# MCU.net
KiCad netlist of a schematic drawn in Altium Designer
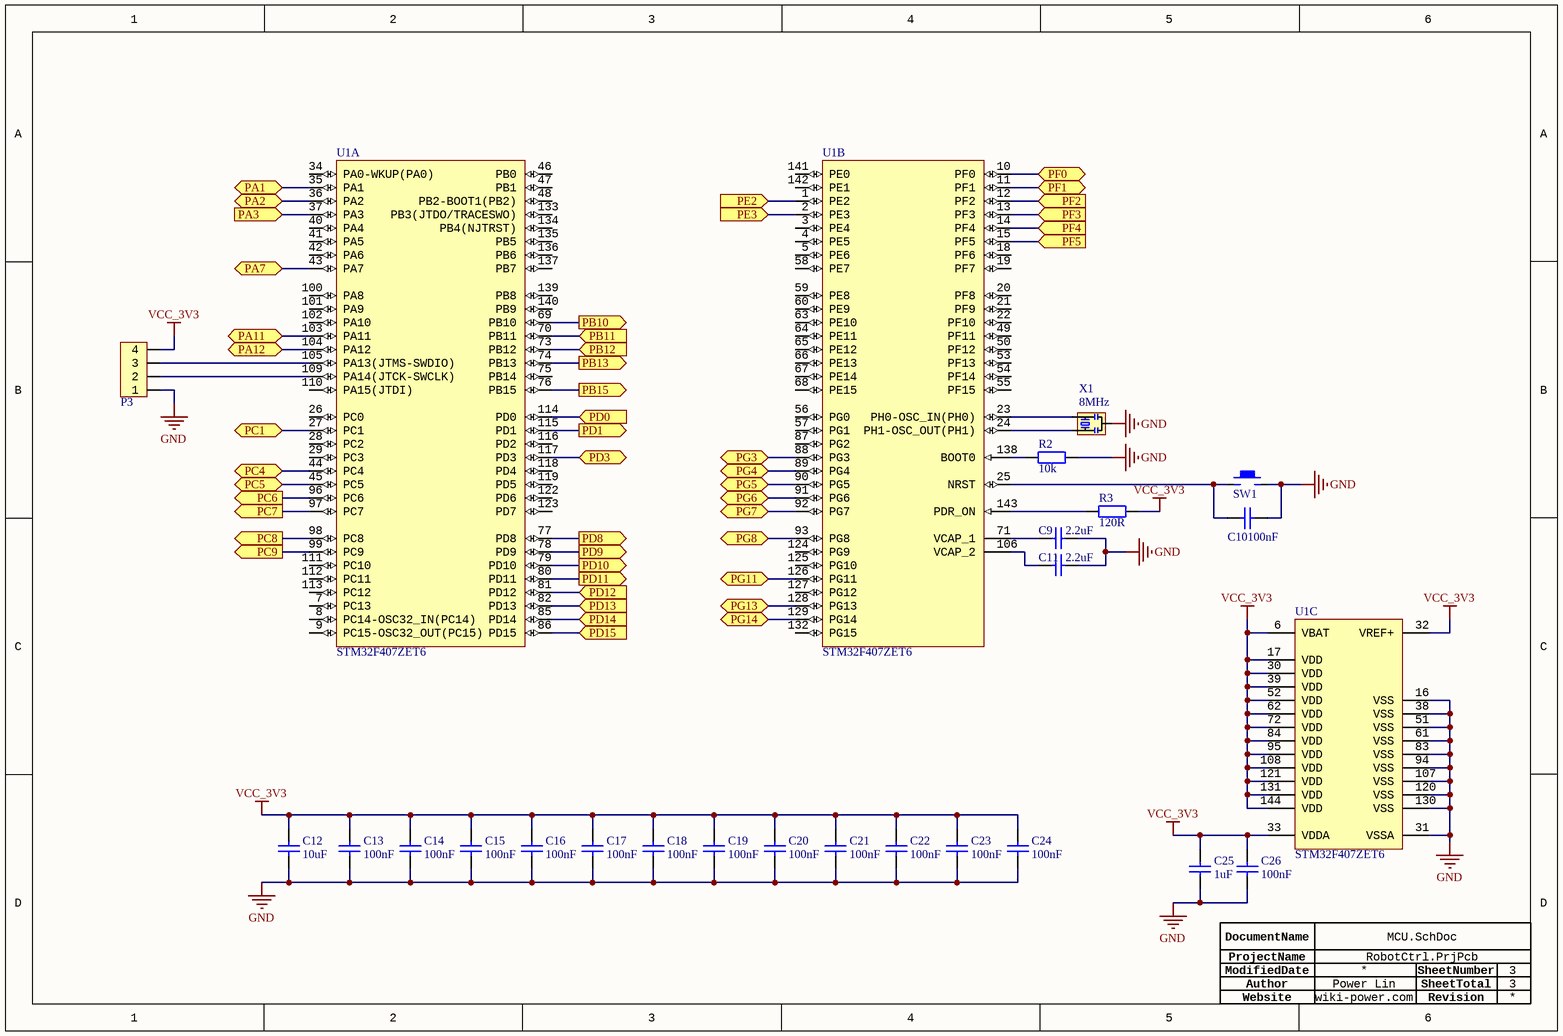
[diagram p0: MCU.SchDoc]

(export (version "E")
  (design (tool "Eeschema 10.0.6"))
  (components
    (comp (ref "C9")
      (value "2.2uF")
      (footprint "CAP-0603")
      (description "贴片电容")
      (libsource (lib "Power_Lib_Altium") (part "CAP"))
    )
    (comp (ref "C10")
      (value "100nF")
      (footprint "CAP-0603")
      (description "贴片电容")
      (libsource (lib "Power_Lib_Altium") (part "CAP"))
    )
    (comp (ref "C11")
      (value "2.2uF")
      (footprint "CAP-0603")
      (description "贴片电容")
      (libsource (lib "Power_Lib_Altium") (part "CAP"))
    )
    (comp (ref "C12")
      (value "10uF")
      (footprint "CAP-0603")
      (description "贴片电容")
      (libsource (lib "Power_Lib_Altium") (part "CAP"))
    )
    (comp (ref "C13")
      (value "100nF")
      (footprint "CAP-0603")
      (description "贴片电容")
      (libsource (lib "Power_Lib_Altium") (part "CAP"))
    )
    (comp (ref "C14")
      (value "100nF")
      (footprint "CAP-0603")
      (description "贴片电容")
      (libsource (lib "Power_Lib_Altium") (part "CAP"))
    )
    (comp (ref "C15")
      (value "100nF")
      (footprint "CAP-0603")
      (description "贴片电容")
      (libsource (lib "Power_Lib_Altium") (part "CAP"))
    )
    (comp (ref "C16")
      (value "100nF")
      (footprint "CAP-0603")
      (description "贴片电容")
      (libsource (lib "Power_Lib_Altium") (part "CAP"))
    )
    (comp (ref "C17")
      (value "100nF")
      (footprint "CAP-0603")
      (description "贴片电容")
      (libsource (lib "Power_Lib_Altium") (part "CAP"))
    )
    (comp (ref "C18")
      (value "100nF")
      (footprint "CAP-0603")
      (description "贴片电容")
      (libsource (lib "Power_Lib_Altium") (part "CAP"))
    )
    (comp (ref "C19")
      (value "100nF")
      (footprint "CAP-0603")
      (description "贴片电容")
      (libsource (lib "Power_Lib_Altium") (part "CAP"))
    )
    (comp (ref "C20")
      (value "100nF")
      (footprint "CAP-0603")
      (description "贴片电容")
      (libsource (lib "Power_Lib_Altium") (part "CAP"))
    )
    (comp (ref "C21")
      (value "100nF")
      (footprint "CAP-0603")
      (description "贴片电容")
      (libsource (lib "Power_Lib_Altium") (part "CAP"))
    )
    (comp (ref "C22")
      (value "100nF")
      (footprint "CAP-0603")
      (description "贴片电容")
      (libsource (lib "Power_Lib_Altium") (part "CAP"))
    )
    (comp (ref "C23")
      (value "100nF")
      (footprint "CAP-0603")
      (description "贴片电容")
      (libsource (lib "Power_Lib_Altium") (part "CAP"))
    )
    (comp (ref "C24")
      (value "100nF")
      (footprint "CAP-0603")
      (description "贴片电容")
      (libsource (lib "Power_Lib_Altium") (part "CAP"))
    )
    (comp (ref "C25")
      (value "1uF")
      (footprint "CAP-0603")
      (description "贴片电容")
      (libsource (lib "Power_Lib_Altium") (part "CAP"))
    )
    (comp (ref "C26")
      (value "100nF")
      (footprint "CAP-0603")
      (description "贴片电容")
      (libsource (lib "Power_Lib_Altium") (part "CAP"))
    )
    (comp (ref "P3")
      (value "HDR1x4_2.54")
      (footprint "HDR1x4_2.54_180")
      (description "Header")
      (libsource (lib "Power_Lib_Altium") (part "HDR1x4_2.54"))
    )
    (comp (ref "R2")
      (value "10k")
      (footprint "R-0603")
      (description "贴片电阻")
      (libsource (lib "Power_Lib_Altium") (part "RES"))
    )
    (comp (ref "R3")
      (value "120R")
      (footprint "R-0603")
      (description "贴片电阻")
      (libsource (lib "Power_Lib_Altium") (part "RES"))
    )
    (comp (ref "SW1")
      (value "KEY")
      (footprint "KEY-4P-4.2*3.4*2.5")
      (description "按键开关")
      (libsource (lib "Power_Lib_Altium") (part "KEY"))
    )
    (comp (ref "U1")
      (value "STM32F407ZET6")
      (footprint "STM-LQFP144_N")
      (fields (field (name "MANUFACTURER") "STMicroelectronics"))
      (libsource (lib "STMicroelectronics STM32 F4") (part "STM32F407ZET6"))
    )
    (comp (ref "X1")
      (value "8MHz")
      (footprint "SMD3213-3P")
      (description "CSTCE8M00G15C99-R0")
      (libsource (lib "Power_Lib_Altium") (part "XTAL"))
    )
  )
  (nets
    (net (code "1") (name "/PA1") (class "Default")
      (node (ref "U1") (pin "35") (pinfunction "PA1_35") (pintype "bidirectional"))
    )
    (net (code "2") (name "/PA2") (class "Default")
      (node (ref "U1") (pin "36") (pinfunction "PA2_36") (pintype "bidirectional"))
    )
    (net (code "3") (name "/PA3") (class "Default")
      (node (ref "U1") (pin "37") (pinfunction "PA3_37") (pintype "bidirectional"))
    )
    (net (code "4") (name "/PA7") (class "Default")
      (node (ref "U1") (pin "43") (pinfunction "PA7_43") (pintype "bidirectional"))
    )
    (net (code "5") (name "/PA11") (class "Default")
      (node (ref "U1") (pin "103") (pinfunction "PA11_103") (pintype "bidirectional"))
    )
    (net (code "6") (name "/PA12") (class "Default")
      (node (ref "U1") (pin "104") (pinfunction "PA12_104") (pintype "bidirectional"))
    )
    (net (code "7") (name "/PB10") (class "Default")
      (node (ref "U1") (pin "69") (pinfunction "PB10_69") (pintype "bidirectional"))
    )
    (net (code "8") (name "/PB11") (class "Default")
      (node (ref "U1") (pin "70") (pinfunction "PB11_70") (pintype "bidirectional"))
    )
    (net (code "9") (name "/PB12") (class "Default")
      (node (ref "U1") (pin "73") (pinfunction "PB12_73") (pintype "bidirectional"))
    )
    (net (code "10") (name "/PB13") (class "Default")
      (node (ref "U1") (pin "74") (pinfunction "PB13_74") (pintype "bidirectional"))
    )
    (net (code "11") (name "/PB15") (class "Default")
      (node (ref "U1") (pin "76") (pinfunction "PB15_76") (pintype "bidirectional"))
    )
    (net (code "12") (name "/PC1") (class "Default")
      (node (ref "U1") (pin "27") (pinfunction "PC1_27") (pintype "bidirectional"))
    )
    (net (code "13") (name "/PC4") (class "Default")
      (node (ref "U1") (pin "44") (pinfunction "PC4_44") (pintype "bidirectional"))
    )
    (net (code "14") (name "/PC5") (class "Default")
      (node (ref "U1") (pin "45") (pinfunction "PC5_45") (pintype "bidirectional"))
    )
    (net (code "15") (name "/PC6") (class "Default")
      (node (ref "U1") (pin "96") (pinfunction "PC6_96") (pintype "bidirectional"))
    )
    (net (code "16") (name "/PC7") (class "Default")
      (node (ref "U1") (pin "97") (pinfunction "PC7_97") (pintype "bidirectional"))
    )
    (net (code "17") (name "/PC8") (class "Default")
      (node (ref "U1") (pin "98") (pinfunction "PC8_98") (pintype "bidirectional"))
    )
    (net (code "18") (name "/PC9") (class "Default")
      (node (ref "U1") (pin "99") (pinfunction "PC9_99") (pintype "bidirectional"))
    )
    (net (code "19") (name "/PD0") (class "Default")
      (node (ref "U1") (pin "114") (pinfunction "PD0_114") (pintype "bidirectional"))
    )
    (net (code "20") (name "/PD1") (class "Default")
      (node (ref "U1") (pin "115") (pinfunction "PD1_115") (pintype "bidirectional"))
    )
    (net (code "21") (name "/PD3") (class "Default")
      (node (ref "U1") (pin "117") (pinfunction "PD3_117") (pintype "bidirectional"))
    )
    (net (code "22") (name "/PD8") (class "Default")
      (node (ref "U1") (pin "77") (pinfunction "PD8_77") (pintype "bidirectional"))
    )
    (net (code "23") (name "/PD9") (class "Default")
      (node (ref "U1") (pin "78") (pinfunction "PD9_78") (pintype "bidirectional"))
    )
    (net (code "24") (name "/PD10") (class "Default")
      (node (ref "U1") (pin "79") (pinfunction "PD10_79") (pintype "bidirectional"))
    )
    (net (code "25") (name "/PD11") (class "Default")
      (node (ref "U1") (pin "80") (pinfunction "PD11_80") (pintype "bidirectional"))
    )
    (net (code "26") (name "/PD12") (class "Default")
      (node (ref "U1") (pin "81") (pinfunction "PD12_81") (pintype "bidirectional"))
    )
    (net (code "27") (name "/PD13") (class "Default")
      (node (ref "U1") (pin "82") (pinfunction "PD13_82") (pintype "bidirectional"))
    )
    (net (code "28") (name "/PD14") (class "Default")
      (node (ref "U1") (pin "85") (pinfunction "PD14_85") (pintype "bidirectional"))
    )
    (net (code "29") (name "/PD15") (class "Default")
      (node (ref "U1") (pin "86") (pinfunction "PD15_86") (pintype "bidirectional"))
    )
    (net (code "30") (name "/PE2") (class "Default")
      (node (ref "U1") (pin "1") (pinfunction "PE2_1") (pintype "bidirectional"))
    )
    (net (code "31") (name "/PE3") (class "Default")
      (node (ref "U1") (pin "2") (pinfunction "PE3_2") (pintype "bidirectional"))
    )
    (net (code "32") (name "/PF0") (class "Default")
      (node (ref "U1") (pin "10") (pinfunction "PF0_10") (pintype "bidirectional"))
    )
    (net (code "33") (name "/PF1") (class "Default")
      (node (ref "U1") (pin "11") (pinfunction "PF1_11") (pintype "bidirectional"))
    )
    (net (code "34") (name "/PF2") (class "Default")
      (node (ref "U1") (pin "12") (pinfunction "PF2_12") (pintype "bidirectional"))
    )
    (net (code "35") (name "/PF3") (class "Default")
      (node (ref "U1") (pin "13") (pinfunction "PF3_13") (pintype "bidirectional"))
    )
    (net (code "36") (name "/PF4") (class "Default")
      (node (ref "U1") (pin "14") (pinfunction "PF4_14") (pintype "bidirectional"))
    )
    (net (code "37") (name "/PF5") (class "Default")
      (node (ref "U1") (pin "15") (pinfunction "PF5_15") (pintype "bidirectional"))
    )
    (net (code "38") (name "/PG3") (class "Default")
      (node (ref "U1") (pin "88") (pinfunction "PG3_88") (pintype "bidirectional"))
    )
    (net (code "39") (name "/PG4") (class "Default")
      (node (ref "U1") (pin "89") (pinfunction "PG4_89") (pintype "bidirectional"))
    )
    (net (code "40") (name "/PG5") (class "Default")
      (node (ref "U1") (pin "90") (pinfunction "PG5_90") (pintype "bidirectional"))
    )
    (net (code "41") (name "/PG6") (class "Default")
      (node (ref "U1") (pin "91") (pinfunction "PG6_91") (pintype "bidirectional"))
    )
    (net (code "42") (name "/PG7") (class "Default")
      (node (ref "U1") (pin "92") (pinfunction "PG7_92") (pintype "bidirectional"))
    )
    (net (code "43") (name "/PG8") (class "Default")
      (node (ref "U1") (pin "93") (pinfunction "PG8_93") (pintype "bidirectional"))
    )
    (net (code "44") (name "/PG11") (class "Default")
      (node (ref "U1") (pin "126") (pinfunction "PG11_126") (pintype "bidirectional"))
    )
    (net (code "45") (name "/PG13") (class "Default")
      (node (ref "U1") (pin "128") (pinfunction "PG13_128") (pintype "bidirectional"))
    )
    (net (code "46") (name "/PG14") (class "Default")
      (node (ref "U1") (pin "129") (pinfunction "PG14_129") (pintype "bidirectional"))
    )
    (net (code "47") (name "GND") (class "Default")
      (node (ref "C10") (pin "1") (pinfunction "1_1") (pintype "passive"))
      (node (ref "C11") (pin "2") (pinfunction "2_2") (pintype "passive"))
      (node (ref "C12") (pin "1") (pinfunction "1_1") (pintype "passive"))
      (node (ref "C13") (pin "1") (pinfunction "1_1") (pintype "passive"))
      (node (ref "C14") (pin "1") (pinfunction "1_1") (pintype "passive"))
      (node (ref "C15") (pin "1") (pinfunction "1_1") (pintype "passive"))
      (node (ref "C16") (pin "1") (pinfunction "1_1") (pintype "passive"))
      (node (ref "C17") (pin "1") (pinfunction "1_1") (pintype "passive"))
      (node (ref "C18") (pin "1") (pinfunction "1_1") (pintype "passive"))
      (node (ref "C19") (pin "1") (pinfunction "1_1") (pintype "passive"))
      (node (ref "C20") (pin "1") (pinfunction "1_1") (pintype "passive"))
      (node (ref "C21") (pin "1") (pinfunction "1_1") (pintype "passive"))
      (node (ref "C22") (pin "1") (pinfunction "1_1") (pintype "passive"))
      (node (ref "C23") (pin "1") (pinfunction "1_1") (pintype "passive"))
      (node (ref "C24") (pin "1") (pinfunction "1_1") (pintype "passive"))
      (node (ref "C25") (pin "1") (pinfunction "1_1") (pintype "passive"))
      (node (ref "C26") (pin "1") (pinfunction "1_1") (pintype "passive"))
      (node (ref "C9") (pin "2") (pinfunction "2_2") (pintype "passive"))
      (node (ref "P3") (pin "1") (pinfunction "1_1") (pintype "passive"))
      (node (ref "R2") (pin "1") (pinfunction "1_1") (pintype "passive"))
      (node (ref "SW1") (pin "2") (pinfunction "2_2") (pintype "passive"))
      (node (ref "U1") (pin "107") (pinfunction "VSS_107") (pintype "power_in"))
      (node (ref "U1") (pin "120") (pinfunction "VSS_120") (pintype "power_in"))
      (node (ref "U1") (pin "130") (pinfunction "VSS_130") (pintype "power_in"))
      (node (ref "U1") (pin "16") (pinfunction "VSS_16") (pintype "power_in"))
      (node (ref "U1") (pin "31") (pinfunction "VSSA_31") (pintype "power_in"))
      (node (ref "U1") (pin "38") (pinfunction "VSS_38") (pintype "power_in"))
      (node (ref "U1") (pin "51") (pinfunction "VSS_51") (pintype "power_in"))
      (node (ref "U1") (pin "61") (pinfunction "VSS_61") (pintype "power_in"))
      (node (ref "U1") (pin "83") (pinfunction "VSS_83") (pintype "power_in"))
      (node (ref "U1") (pin "94") (pinfunction "VSS_94") (pintype "power_in"))
      (node (ref "X1") (pin "2") (pinfunction "GND_2") (pintype "passive"))
    )
    (net (code "48") (name "Net-(U1A-PA13(JTMS-SWDIO))") (class "Default")
      (node (ref "P3") (pin "3") (pinfunction "3_3") (pintype "passive"))
      (node (ref "U1") (pin "105") (pinfunction "PA13(JTMS-SWDIO)_105") (pintype "bidirectional"))
    )
    (net (code "49") (name "Net-(U1A-PA14(JTCK-SWCLK))") (class "Default")
      (node (ref "P3") (pin "2") (pinfunction "2_2") (pintype "passive"))
      (node (ref "U1") (pin "109") (pinfunction "PA14(JTCK-SWCLK)_109") (pintype "bidirectional"))
    )
    (net (code "50") (name "Net-(U1B-BOOT0)") (class "Default")
      (node (ref "R2") (pin "2") (pinfunction "2_2") (pintype "passive"))
      (node (ref "U1") (pin "138") (pinfunction "BOOT0_138") (pintype "input"))
    )
    (net (code "51") (name "Net-(U1B-NRST)") (class "Default")
      (node (ref "C10") (pin "2") (pinfunction "2_2") (pintype "passive"))
      (node (ref "SW1") (pin "1") (pinfunction "1_1") (pintype "passive"))
      (node (ref "U1") (pin "25") (pinfunction "NRST_25") (pintype "bidirectional"))
    )
    (net (code "52") (name "Net-(U1B-PDR_ON)") (class "Default")
      (node (ref "R3") (pin "2") (pinfunction "2_2") (pintype "passive"))
      (node (ref "U1") (pin "143") (pinfunction "PDR_ON_143") (pintype "input"))
    )
    (net (code "53") (name "Net-(U1B-PH0-OSC_IN(PH0))") (class "Default")
      (node (ref "U1") (pin "23") (pinfunction "PH0-OSC_IN(PH0)_23") (pintype "bidirectional"))
      (node (ref "X1") (pin "3") (pinfunction "OSC2_3") (pintype "passive"))
    )
    (net (code "54") (name "Net-(U1B-PH1-OSC_OUT(PH1))") (class "Default")
      (node (ref "U1") (pin "24") (pinfunction "PH1-OSC_OUT(PH1)_24") (pintype "bidirectional"))
      (node (ref "X1") (pin "1") (pinfunction "OSC1_1") (pintype "passive"))
    )
    (net (code "55") (name "Net-(U1B-VCAP_1)") (class "Default")
      (node (ref "C9") (pin "1") (pinfunction "1_1") (pintype "passive"))
      (node (ref "U1") (pin "71") (pinfunction "VCAP_1_71") (pintype "power_in"))
    )
    (net (code "56") (name "Net-(U1B-VCAP_2)") (class "Default")
      (node (ref "C11") (pin "1") (pinfunction "1_1") (pintype "passive"))
      (node (ref "U1") (pin "106") (pinfunction "VCAP_2_106") (pintype "power_in"))
    )
    (net (code "57") (name "VCC_3V3") (class "Default")
      (node (ref "C12") (pin "2") (pinfunction "2_2") (pintype "passive"))
      (node (ref "C13") (pin "2") (pinfunction "2_2") (pintype "passive"))
      (node (ref "C14") (pin "2") (pinfunction "2_2") (pintype "passive"))
      (node (ref "C15") (pin "2") (pinfunction "2_2") (pintype "passive"))
      (node (ref "C16") (pin "2") (pinfunction "2_2") (pintype "passive"))
      (node (ref "C17") (pin "2") (pinfunction "2_2") (pintype "passive"))
      (node (ref "C18") (pin "2") (pinfunction "2_2") (pintype "passive"))
      (node (ref "C19") (pin "2") (pinfunction "2_2") (pintype "passive"))
      (node (ref "C20") (pin "2") (pinfunction "2_2") (pintype "passive"))
      (node (ref "C21") (pin "2") (pinfunction "2_2") (pintype "passive"))
      (node (ref "C22") (pin "2") (pinfunction "2_2") (pintype "passive"))
      (node (ref "C23") (pin "2") (pinfunction "2_2") (pintype "passive"))
      (node (ref "C24") (pin "2") (pinfunction "2_2") (pintype "passive"))
      (node (ref "C25") (pin "2") (pinfunction "2_2") (pintype "passive"))
      (node (ref "C26") (pin "2") (pinfunction "2_2") (pintype "passive"))
      (node (ref "P3") (pin "4") (pinfunction "4_4") (pintype "passive"))
      (node (ref "R3") (pin "1") (pinfunction "1_1") (pintype "passive"))
      (node (ref "U1") (pin "108") (pinfunction "VDD_108") (pintype "power_in"))
      (node (ref "U1") (pin "121") (pinfunction "VDD_121") (pintype "power_in"))
      (node (ref "U1") (pin "131") (pinfunction "VDD_131") (pintype "power_in"))
      (node (ref "U1") (pin "144") (pinfunction "VDD_144") (pintype "power_in"))
      (node (ref "U1") (pin "17") (pinfunction "VDD_17") (pintype "power_in"))
      (node (ref "U1") (pin "30") (pinfunction "VDD_30") (pintype "power_in"))
      (node (ref "U1") (pin "32") (pinfunction "VREF+_32") (pintype "power_in"))
      (node (ref "U1") (pin "33") (pinfunction "VDDA_33") (pintype "power_in"))
      (node (ref "U1") (pin "39") (pinfunction "VDD_39") (pintype "power_in"))
      (node (ref "U1") (pin "52") (pinfunction "VDD_52") (pintype "power_in"))
      (node (ref "U1") (pin "6") (pinfunction "VBAT_6") (pintype "power_in"))
      (node (ref "U1") (pin "62") (pinfunction "VDD_62") (pintype "power_in"))
      (node (ref "U1") (pin "72") (pinfunction "VDD_72") (pintype "power_in"))
      (node (ref "U1") (pin "84") (pinfunction "VDD_84") (pintype "power_in"))
      (node (ref "U1") (pin "95") (pinfunction "VDD_95") (pintype "power_in"))
    )
    (net (code "58") (name "unconnected-(U1A-PA0-WKUP(PA0)-Pad34)") (class "Default")
      (node (ref "U1") (pin "34") (pinfunction "PA0-WKUP(PA0)_34") (pintype "bidirectional"))
    )
    (net (code "59") (name "unconnected-(U1A-PA4-Pad40)") (class "Default")
      (node (ref "U1") (pin "40") (pinfunction "PA4_40") (pintype "bidirectional"))
    )
    (net (code "60") (name "unconnected-(U1A-PA5-Pad41)") (class "Default")
      (node (ref "U1") (pin "41") (pinfunction "PA5_41") (pintype "bidirectional"))
    )
    (net (code "61") (name "unconnected-(U1A-PA6-Pad42)") (class "Default")
      (node (ref "U1") (pin "42") (pinfunction "PA6_42") (pintype "bidirectional"))
    )
    (net (code "62") (name "unconnected-(U1A-PA8-Pad100)") (class "Default")
      (node (ref "U1") (pin "100") (pinfunction "PA8_100") (pintype "bidirectional"))
    )
    (net (code "63") (name "unconnected-(U1A-PA9-Pad101)") (class "Default")
      (node (ref "U1") (pin "101") (pinfunction "PA9_101") (pintype "bidirectional"))
    )
    (net (code "64") (name "unconnected-(U1A-PA10-Pad102)") (class "Default")
      (node (ref "U1") (pin "102") (pinfunction "PA10_102") (pintype "bidirectional"))
    )
    (net (code "65") (name "unconnected-(U1A-PA15(JTDI)-Pad110)") (class "Default")
      (node (ref "U1") (pin "110") (pinfunction "PA15(JTDI)_110") (pintype "bidirectional"))
    )
    (net (code "66") (name "unconnected-(U1A-PB0-Pad46)") (class "Default")
      (node (ref "U1") (pin "46") (pinfunction "PB0_46") (pintype "bidirectional"))
    )
    (net (code "67") (name "unconnected-(U1A-PB1-Pad47)") (class "Default")
      (node (ref "U1") (pin "47") (pinfunction "PB1_47") (pintype "bidirectional"))
    )
    (net (code "68") (name "unconnected-(U1A-PB2-BOOT1(PB2)-Pad48)") (class "Default")
      (node (ref "U1") (pin "48") (pinfunction "PB2-BOOT1(PB2)_48") (pintype "bidirectional"))
    )
    (net (code "69") (name "unconnected-(U1A-PB3(JTDO{slash}TRACESWO)-Pad133)") (class "Default")
      (node (ref "U1") (pin "133") (pinfunction "PB3(JTDO/TRACESWO)_133") (pintype "bidirectional"))
    )
    (net (code "70") (name "unconnected-(U1A-PB4(NJTRST)-Pad134)") (class "Default")
      (node (ref "U1") (pin "134") (pinfunction "PB4(NJTRST)_134") (pintype "bidirectional"))
    )
    (net (code "71") (name "unconnected-(U1A-PB5-Pad135)") (class "Default")
      (node (ref "U1") (pin "135") (pinfunction "PB5_135") (pintype "bidirectional"))
    )
    (net (code "72") (name "unconnected-(U1A-PB6-Pad136)") (class "Default")
      (node (ref "U1") (pin "136") (pinfunction "PB6_136") (pintype "bidirectional"))
    )
    (net (code "73") (name "unconnected-(U1A-PB7-Pad137)") (class "Default")
      (node (ref "U1") (pin "137") (pinfunction "PB7_137") (pintype "bidirectional"))
    )
    (net (code "74") (name "unconnected-(U1A-PB8-Pad139)") (class "Default")
      (node (ref "U1") (pin "139") (pinfunction "PB8_139") (pintype "bidirectional"))
    )
    (net (code "75") (name "unconnected-(U1A-PB9-Pad140)") (class "Default")
      (node (ref "U1") (pin "140") (pinfunction "PB9_140") (pintype "bidirectional"))
    )
    (net (code "76") (name "unconnected-(U1A-PB14-Pad75)") (class "Default")
      (node (ref "U1") (pin "75") (pinfunction "PB14_75") (pintype "bidirectional"))
    )
    (net (code "77") (name "unconnected-(U1A-PC0-Pad26)") (class "Default")
      (node (ref "U1") (pin "26") (pinfunction "PC0_26") (pintype "bidirectional"))
    )
    (net (code "78") (name "unconnected-(U1A-PC2-Pad28)") (class "Default")
      (node (ref "U1") (pin "28") (pinfunction "PC2_28") (pintype "bidirectional"))
    )
    (net (code "79") (name "unconnected-(U1A-PC3-Pad29)") (class "Default")
      (node (ref "U1") (pin "29") (pinfunction "PC3_29") (pintype "bidirectional"))
    )
    (net (code "80") (name "unconnected-(U1A-PC10-Pad111)") (class "Default")
      (node (ref "U1") (pin "111") (pinfunction "PC10_111") (pintype "bidirectional"))
    )
    (net (code "81") (name "unconnected-(U1A-PC11-Pad112)") (class "Default")
      (node (ref "U1") (pin "112") (pinfunction "PC11_112") (pintype "bidirectional"))
    )
    (net (code "82") (name "unconnected-(U1A-PC12-Pad113)") (class "Default")
      (node (ref "U1") (pin "113") (pinfunction "PC12_113") (pintype "bidirectional"))
    )
    (net (code "83") (name "unconnected-(U1A-PC13-Pad7)") (class "Default")
      (node (ref "U1") (pin "7") (pinfunction "PC13_7") (pintype "bidirectional"))
    )
    (net (code "84") (name "unconnected-(U1A-PC14-OSC32_IN(PC14)-Pad8)") (class "Default")
      (node (ref "U1") (pin "8") (pinfunction "PC14-OSC32_IN(PC14)_8") (pintype "bidirectional"))
    )
    (net (code "85") (name "unconnected-(U1A-PC15-OSC32_OUT(PC15)-Pad9)") (class "Default")
      (node (ref "U1") (pin "9") (pinfunction "PC15-OSC32_OUT(PC15)_9") (pintype "bidirectional"))
    )
    (net (code "86") (name "unconnected-(U1A-PD2-Pad116)") (class "Default")
      (node (ref "U1") (pin "116") (pinfunction "PD2_116") (pintype "bidirectional"))
    )
    (net (code "87") (name "unconnected-(U1A-PD4-Pad118)") (class "Default")
      (node (ref "U1") (pin "118") (pinfunction "PD4_118") (pintype "bidirectional"))
    )
    (net (code "88") (name "unconnected-(U1A-PD5-Pad119)") (class "Default")
      (node (ref "U1") (pin "119") (pinfunction "PD5_119") (pintype "bidirectional"))
    )
    (net (code "89") (name "unconnected-(U1A-PD6-Pad122)") (class "Default")
      (node (ref "U1") (pin "122") (pinfunction "PD6_122") (pintype "bidirectional"))
    )
    (net (code "90") (name "unconnected-(U1A-PD7-Pad123)") (class "Default")
      (node (ref "U1") (pin "123") (pinfunction "PD7_123") (pintype "bidirectional"))
    )
    (net (code "91") (name "unconnected-(U1B-PE0-Pad141)") (class "Default")
      (node (ref "U1") (pin "141") (pinfunction "PE0_141") (pintype "bidirectional"))
    )
    (net (code "92") (name "unconnected-(U1B-PE1-Pad142)") (class "Default")
      (node (ref "U1") (pin "142") (pinfunction "PE1_142") (pintype "bidirectional"))
    )
    (net (code "93") (name "unconnected-(U1B-PE4-Pad3)") (class "Default")
      (node (ref "U1") (pin "3") (pinfunction "PE4_3") (pintype "bidirectional"))
    )
    (net (code "94") (name "unconnected-(U1B-PE5-Pad4)") (class "Default")
      (node (ref "U1") (pin "4") (pinfunction "PE5_4") (pintype "bidirectional"))
    )
    (net (code "95") (name "unconnected-(U1B-PE6-Pad5)") (class "Default")
      (node (ref "U1") (pin "5") (pinfunction "PE6_5") (pintype "bidirectional"))
    )
    (net (code "96") (name "unconnected-(U1B-PE7-Pad58)") (class "Default")
      (node (ref "U1") (pin "58") (pinfunction "PE7_58") (pintype "bidirectional"))
    )
    (net (code "97") (name "unconnected-(U1B-PE8-Pad59)") (class "Default")
      (node (ref "U1") (pin "59") (pinfunction "PE8_59") (pintype "bidirectional"))
    )
    (net (code "98") (name "unconnected-(U1B-PE9-Pad60)") (class "Default")
      (node (ref "U1") (pin "60") (pinfunction "PE9_60") (pintype "bidirectional"))
    )
    (net (code "99") (name "unconnected-(U1B-PE10-Pad63)") (class "Default")
      (node (ref "U1") (pin "63") (pinfunction "PE10_63") (pintype "bidirectional"))
    )
    (net (code "100") (name "unconnected-(U1B-PE11-Pad64)") (class "Default")
      (node (ref "U1") (pin "64") (pinfunction "PE11_64") (pintype "bidirectional"))
    )
    (net (code "101") (name "unconnected-(U1B-PE12-Pad65)") (class "Default")
      (node (ref "U1") (pin "65") (pinfunction "PE12_65") (pintype "bidirectional"))
    )
    (net (code "102") (name "unconnected-(U1B-PE13-Pad66)") (class "Default")
      (node (ref "U1") (pin "66") (pinfunction "PE13_66") (pintype "bidirectional"))
    )
    (net (code "103") (name "unconnected-(U1B-PE14-Pad67)") (class "Default")
      (node (ref "U1") (pin "67") (pinfunction "PE14_67") (pintype "bidirectional"))
    )
    (net (code "104") (name "unconnected-(U1B-PE15-Pad68)") (class "Default")
      (node (ref "U1") (pin "68") (pinfunction "PE15_68") (pintype "bidirectional"))
    )
    (net (code "105") (name "unconnected-(U1B-PF6-Pad18)") (class "Default")
      (node (ref "U1") (pin "18") (pinfunction "PF6_18") (pintype "bidirectional"))
    )
    (net (code "106") (name "unconnected-(U1B-PF7-Pad19)") (class "Default")
      (node (ref "U1") (pin "19") (pinfunction "PF7_19") (pintype "bidirectional"))
    )
    (net (code "107") (name "unconnected-(U1B-PF8-Pad20)") (class "Default")
      (node (ref "U1") (pin "20") (pinfunction "PF8_20") (pintype "bidirectional"))
    )
    (net (code "108") (name "unconnected-(U1B-PF9-Pad21)") (class "Default")
      (node (ref "U1") (pin "21") (pinfunction "PF9_21") (pintype "bidirectional"))
    )
    (net (code "109") (name "unconnected-(U1B-PF10-Pad22)") (class "Default")
      (node (ref "U1") (pin "22") (pinfunction "PF10_22") (pintype "bidirectional"))
    )
    (net (code "110") (name "unconnected-(U1B-PF11-Pad49)") (class "Default")
      (node (ref "U1") (pin "49") (pinfunction "PF11_49") (pintype "bidirectional"))
    )
    (net (code "111") (name "unconnected-(U1B-PF12-Pad50)") (class "Default")
      (node (ref "U1") (pin "50") (pinfunction "PF12_50") (pintype "bidirectional"))
    )
    (net (code "112") (name "unconnected-(U1B-PF13-Pad53)") (class "Default")
      (node (ref "U1") (pin "53") (pinfunction "PF13_53") (pintype "bidirectional"))
    )
    (net (code "113") (name "unconnected-(U1B-PF14-Pad54)") (class "Default")
      (node (ref "U1") (pin "54") (pinfunction "PF14_54") (pintype "bidirectional"))
    )
    (net (code "114") (name "unconnected-(U1B-PF15-Pad55)") (class "Default")
      (node (ref "U1") (pin "55") (pinfunction "PF15_55") (pintype "bidirectional"))
    )
    (net (code "115") (name "unconnected-(U1B-PG0-Pad56)") (class "Default")
      (node (ref "U1") (pin "56") (pinfunction "PG0_56") (pintype "bidirectional"))
    )
    (net (code "116") (name "unconnected-(U1B-PG1-Pad57)") (class "Default")
      (node (ref "U1") (pin "57") (pinfunction "PG1_57") (pintype "bidirectional"))
    )
    (net (code "117") (name "unconnected-(U1B-PG2-Pad87)") (class "Default")
      (node (ref "U1") (pin "87") (pinfunction "PG2_87") (pintype "bidirectional"))
    )
    (net (code "118") (name "unconnected-(U1B-PG9-Pad124)") (class "Default")
      (node (ref "U1") (pin "124") (pinfunction "PG9_124") (pintype "bidirectional"))
    )
    (net (code "119") (name "unconnected-(U1B-PG10-Pad125)") (class "Default")
      (node (ref "U1") (pin "125") (pinfunction "PG10_125") (pintype "bidirectional"))
    )
    (net (code "120") (name "unconnected-(U1B-PG12-Pad127)") (class "Default")
      (node (ref "U1") (pin "127") (pinfunction "PG12_127") (pintype "bidirectional"))
    )
    (net (code "121") (name "unconnected-(U1B-PG15-Pad132)") (class "Default")
      (node (ref "U1") (pin "132") (pinfunction "PG15_132") (pintype "bidirectional"))
    )
  )
)
